# Filter_Rectifier_ADC.net
KiCad netlist of a schematic drawn in EAGLE
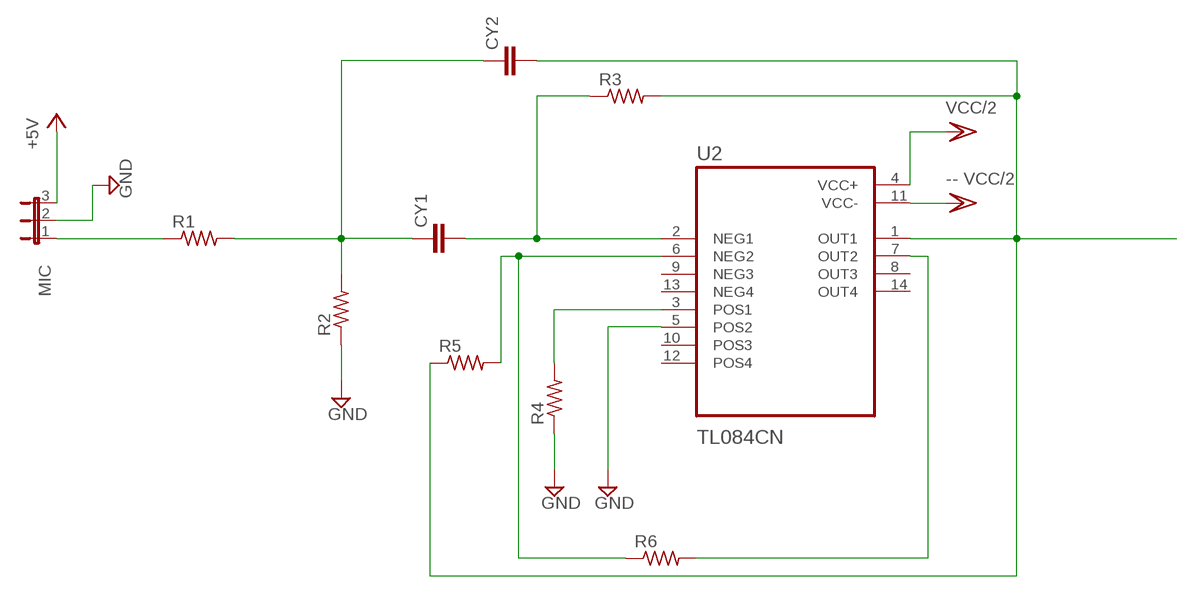
[diagram p0: schematic, sheet 1]

(export (version "E")
  (design (tool "Eeschema 10.0.6"))
  (components
    (comp (ref "CY1")
      (value "CYYC7B5")
      (footprint "eagle-import:YC7B5")
      (libsource (lib "eagle-import") (part "CYYC7B5"))
    )
    (comp (ref "CY2")
      (value "CYYC7B5")
      (footprint "eagle-import:YC7B5")
      (libsource (lib "eagle-import") (part "CYYC7B5"))
    )
    (comp (ref "MIC")
      (value "JP2W")
      (footprint "eagle-import:JP2W")
      (libsource (lib "eagle-import") (part "JP2W"))
    )
    (comp (ref "R1")
      (value "R-US_0204/7")
      (footprint "eagle-import:0204_7")
      (libsource (lib "eagle-import") (part "R-US_0204/7"))
    )
    (comp (ref "R2")
      (value "R-US_0204/7")
      (footprint "eagle-import:0204_7")
      (libsource (lib "eagle-import") (part "R-US_0204/7"))
    )
    (comp (ref "R3")
      (value "R-US_0204/7")
      (footprint "eagle-import:0204_7")
      (libsource (lib "eagle-import") (part "R-US_0204/7"))
    )
    (comp (ref "R4")
      (value "R-US_0204/7")
      (footprint "eagle-import:0204_7")
      (libsource (lib "eagle-import") (part "R-US_0204/7"))
    )
    (comp (ref "R5")
      (value "R-US_0204/7")
      (footprint "eagle-import:0204_7")
      (libsource (lib "eagle-import") (part "R-US_0204/7"))
    )
    (comp (ref "R6")
      (value "R-US_0204/7")
      (footprint "eagle-import:0204_7")
      (libsource (lib "eagle-import") (part "R-US_0204/7"))
    )
    (comp (ref "U2")
      (value "TL084CN")
      (footprint "eagle-import:DIP794W45P254L1969H508Q14")
      (fields (field (name "DIGI-KEY_PART_NUMBER") "296-1784-5-ND") (field (name "MF") "Texas Instruments"))
      (libsource (lib "eagle-import") (part "TL084CN"))
    )
  )
  (nets
    (net (code "1") (name "+5V") (class "Default")
      (node (ref "MIC") (pin "3") (pinfunction "3_3") (pintype "passive"))
    )
    (net (code "2") (name "-- VCC{slash}2") (class "Default")
      (node (ref "U2") (pin "11") (pinfunction "VCC-_11") (pintype "power_in"))
      (node (ref "U2") (pin "4") (pinfunction "VCC+_4") (pintype "power_in"))
    )
    (net (code "3") (name "GND") (class "Default")
      (node (ref "MIC") (pin "2") (pinfunction "2_2") (pintype "passive"))
      (node (ref "R2") (pin "1") (pinfunction "1_1") (pintype "passive"))
      (node (ref "R4") (pin "1") (pinfunction "1_1") (pintype "passive"))
      (node (ref "U2") (pin "5") (pinfunction "POS2_5") (pintype "input"))
    )
    (net (code "4") (name "Net-(CY1-Pad1)") (class "Default")
      (node (ref "CY1") (pin "1") (pinfunction "1_1") (pintype "passive"))
      (node (ref "CY2") (pin "1") (pinfunction "1_1") (pintype "passive"))
      (node (ref "R1") (pin "2") (pinfunction "2_2") (pintype "passive"))
      (node (ref "R2") (pin "2") (pinfunction "2_2") (pintype "passive"))
    )
    (net (code "5") (name "Net-(MIC-Pad1)") (class "Default")
      (node (ref "MIC") (pin "1") (pinfunction "1_1") (pintype "passive"))
      (node (ref "R1") (pin "1") (pinfunction "1_1") (pintype "passive"))
    )
    (net (code "6") (name "Net-(U2-NEG1)") (class "Default")
      (node (ref "CY1") (pin "2") (pinfunction "2_2") (pintype "passive"))
      (node (ref "R3") (pin "1") (pinfunction "1_1") (pintype "passive"))
      (node (ref "U2") (pin "2") (pinfunction "NEG1_2") (pintype "input"))
    )
    (net (code "7") (name "Net-(U2-NEG2)") (class "Default")
      (node (ref "R5") (pin "2") (pinfunction "2_2") (pintype "passive"))
      (node (ref "R6") (pin "1") (pinfunction "1_1") (pintype "passive"))
      (node (ref "U2") (pin "6") (pinfunction "NEG2_6") (pintype "input"))
    )
    (net (code "8") (name "Net-(U2-OUT1)") (class "Default")
      (node (ref "CY2") (pin "2") (pinfunction "2_2") (pintype "passive"))
      (node (ref "R3") (pin "2") (pinfunction "2_2") (pintype "passive"))
      (node (ref "R5") (pin "1") (pinfunction "1_1") (pintype "passive"))
      (node (ref "U2") (pin "1") (pinfunction "OUT1_1") (pintype "output"))
    )
    (net (code "9") (name "Net-(U2-OUT2)") (class "Default")
      (node (ref "R6") (pin "2") (pinfunction "2_2") (pintype "passive"))
      (node (ref "U2") (pin "7") (pinfunction "OUT2_7") (pintype "output"))
    )
    (net (code "10") (name "Net-(U2-POS1)") (class "Default")
      (node (ref "R4") (pin "2") (pinfunction "2_2") (pintype "passive"))
      (node (ref "U2") (pin "3") (pinfunction "POS1_3") (pintype "input"))
    )
    (net (code "11") (name "unconnected-(U2-NEG3-Pad9)") (class "Default")
      (node (ref "U2") (pin "9") (pinfunction "NEG3_9") (pintype "input"))
    )
    (net (code "12") (name "unconnected-(U2-NEG4-Pad13)") (class "Default")
      (node (ref "U2") (pin "13") (pinfunction "NEG4_13") (pintype "input"))
    )
    (net (code "13") (name "unconnected-(U2-OUT3-Pad8)") (class "Default")
      (node (ref "U2") (pin "8") (pinfunction "OUT3_8") (pintype "output"))
    )
    (net (code "14") (name "unconnected-(U2-OUT4-Pad14)") (class "Default")
      (node (ref "U2") (pin "14") (pinfunction "OUT4_14") (pintype "output"))
    )
    (net (code "15") (name "unconnected-(U2-POS3-Pad10)") (class "Default")
      (node (ref "U2") (pin "10") (pinfunction "POS3_10") (pintype "input"))
    )
    (net (code "16") (name "unconnected-(U2-POS4-Pad12)") (class "Default")
      (node (ref "U2") (pin "12") (pinfunction "POS4_12") (pintype "input"))
    )
  )
)
